# Micro_Bit_Gamer_Bit.net
KiCad netlist of a schematic drawn in EAGLE
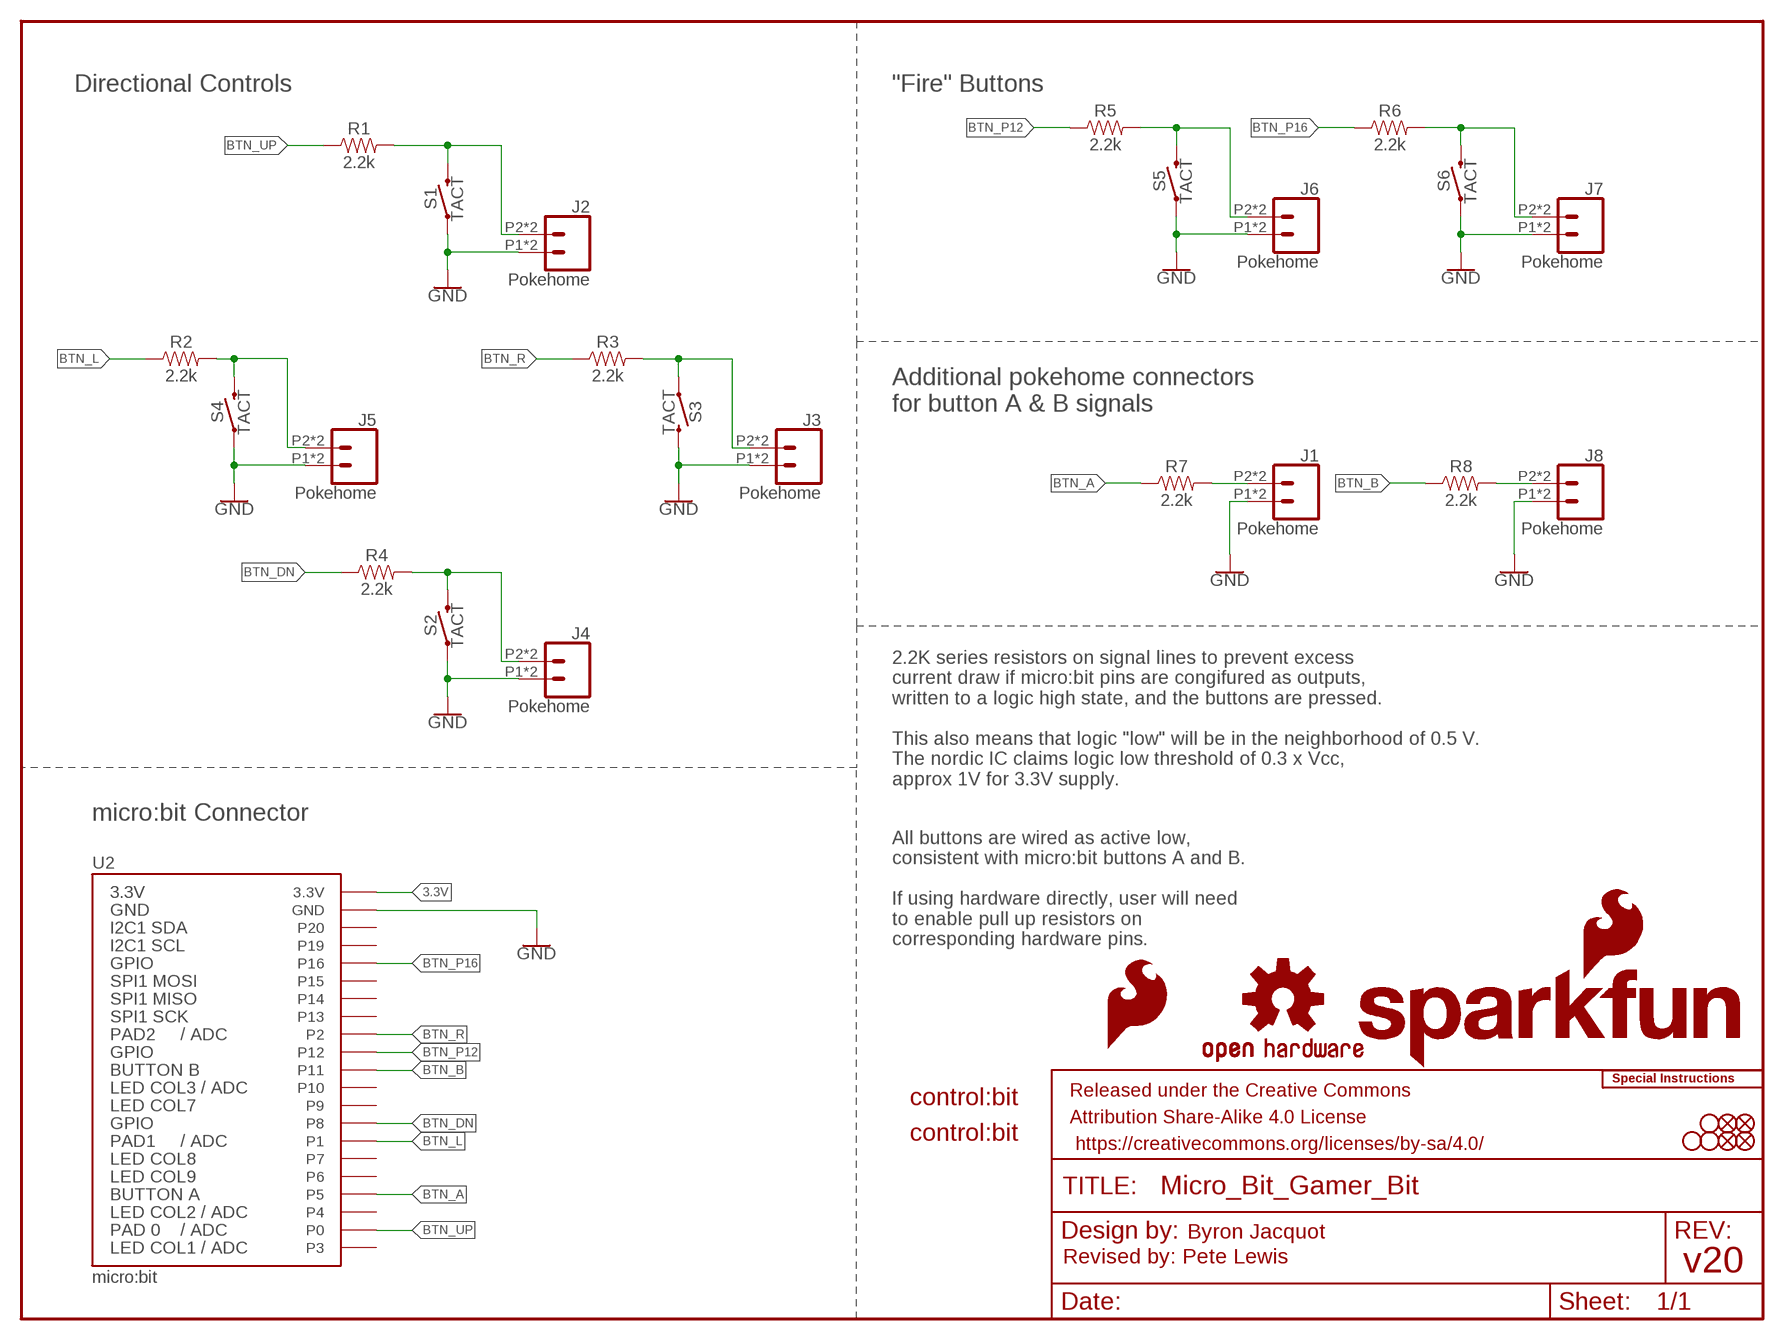
[diagram p0: schematic, sheet 1]

(export (version "E")
  (design (tool "Eeschema 10.0.6"))
  (components
    (comp (ref "FD1")
      (value "FIDUCIALUFIDUCIAL")
      (footprint "eagle-import:FIDUCIAL-MICRO")
      (libsource (lib "eagle-import") (part "FIDUCIALUFIDUCIAL"))
    )
    (comp (ref "FD2")
      (value "FIDUCIALUFIDUCIAL")
      (footprint "eagle-import:FIDUCIAL-MICRO")
      (libsource (lib "eagle-import") (part "FIDUCIALUFIDUCIAL"))
    )
    (comp (ref "FD3")
      (value "FIDUCIALUFIDUCIAL")
      (footprint "eagle-import:FIDUCIAL-MICRO")
      (libsource (lib "eagle-import") (part "FIDUCIALUFIDUCIAL"))
    )
    (comp (ref "FD4")
      (value "FIDUCIALUFIDUCIAL")
      (footprint "eagle-import:FIDUCIAL-MICRO")
      (libsource (lib "eagle-import") (part "FIDUCIALUFIDUCIAL"))
    )
    (comp (ref "FRAME1")
      (value "FRAME-LETTER")
      (footprint "eagle-import:CREATIVE_COMMONS")
      (libsource (lib "eagle-import") (part "FRAME-LETTER"))
    )
    (comp (ref "H1")
      (value "STAND-OFF")
      (footprint "eagle-import:STAND-OFF")
      (libsource (lib "eagle-import") (part "STAND-OFF"))
    )
    (comp (ref "H2")
      (value "STAND-OFF")
      (footprint "eagle-import:STAND-OFF")
      (libsource (lib "eagle-import") (part "STAND-OFF"))
    )
    (comp (ref "H3")
      (value "STAND-OFF")
      (footprint "eagle-import:STAND-OFF")
      (libsource (lib "eagle-import") (part "STAND-OFF"))
    )
    (comp (ref "J1")
      (value "Pokehome")
      (footprint "eagle-import:1X02_POKEHOME")
      (libsource (lib "eagle-import") (part "CONN_02SMALL_POKEHOME"))
    )
    (comp (ref "J2")
      (value "Pokehome")
      (footprint "eagle-import:1X02_POKEHOME")
      (libsource (lib "eagle-import") (part "CONN_02SMALL_POKEHOME"))
    )
    (comp (ref "J3")
      (value "Pokehome")
      (footprint "eagle-import:1X02_POKEHOME")
      (libsource (lib "eagle-import") (part "CONN_02SMALL_POKEHOME"))
    )
    (comp (ref "J4")
      (value "Pokehome")
      (footprint "eagle-import:1X02_POKEHOME")
      (libsource (lib "eagle-import") (part "CONN_02SMALL_POKEHOME"))
    )
    (comp (ref "J5")
      (value "Pokehome")
      (footprint "eagle-import:1X02_POKEHOME")
      (libsource (lib "eagle-import") (part "CONN_02SMALL_POKEHOME"))
    )
    (comp (ref "J6")
      (value "Pokehome")
      (footprint "eagle-import:1X02_POKEHOME")
      (libsource (lib "eagle-import") (part "CONN_02SMALL_POKEHOME"))
    )
    (comp (ref "J7")
      (value "Pokehome")
      (footprint "eagle-import:1X02_POKEHOME")
      (libsource (lib "eagle-import") (part "CONN_02SMALL_POKEHOME"))
    )
    (comp (ref "J8")
      (value "Pokehome")
      (footprint "eagle-import:1X02_POKEHOME")
      (libsource (lib "eagle-import") (part "CONN_02SMALL_POKEHOME"))
    )
    (comp (ref "LOGO1")
      (value "SFE_LOGO_FLAME.2_INCH")
      (footprint "eagle-import:SFE_LOGO_FLAME_.2")
      (libsource (lib "eagle-import") (part "SFE_LOGO_FLAME.2_INCH"))
    )
    (comp (ref "LOGO2")
      (value "OSHW-LOGOL")
      (footprint "eagle-import:OSHW-LOGO-L")
      (libsource (lib "eagle-import") (part "OSHW-LOGOL"))
    )
    (comp (ref "LOGO3")
      (value "SFE_LOGO_NAME_FLAME.3_INCH")
      (footprint "eagle-import:SFE_LOGO_NAME_FLAME_.3")
      (libsource (lib "eagle-import") (part "SFE_LOGO_NAME_FLAME.3_INCH"))
    )
    (comp (ref "R1")
      (value "2.2k")
      (footprint "eagle-import:0603")
      (libsource (lib "eagle-import") (part "2.2KOHM-0603-1/10W-1%"))
    )
    (comp (ref "R2")
      (value "2.2k")
      (footprint "eagle-import:0603")
      (libsource (lib "eagle-import") (part "2.2KOHM-0603-1/10W-1%"))
    )
    (comp (ref "R3")
      (value "2.2k")
      (footprint "eagle-import:0603")
      (libsource (lib "eagle-import") (part "2.2KOHM-0603-1/10W-1%"))
    )
    (comp (ref "R4")
      (value "2.2k")
      (footprint "eagle-import:0603")
      (libsource (lib "eagle-import") (part "2.2KOHM-0603-1/10W-1%"))
    )
    (comp (ref "R5")
      (value "2.2k")
      (footprint "eagle-import:0603")
      (libsource (lib "eagle-import") (part "2.2KOHM-0603-1/10W-1%"))
    )
    (comp (ref "R6")
      (value "2.2k")
      (footprint "eagle-import:0603")
      (libsource (lib "eagle-import") (part "2.2KOHM-0603-1/10W-1%"))
    )
    (comp (ref "R7")
      (value "2.2k")
      (footprint "eagle-import:0603")
      (libsource (lib "eagle-import") (part "2.2KOHM-0603-1/10W-1%"))
    )
    (comp (ref "R8")
      (value "2.2k")
      (footprint "eagle-import:0603")
      (libsource (lib "eagle-import") (part "2.2KOHM-0603-1/10W-1%"))
    )
    (comp (ref "S1")
      (value "TACT")
      (footprint "eagle-import:TACTILE_SWITCH_SMD_12MM")
      (libsource (lib "eagle-import") (part "MOMENTARY-SWITCH-SPST-SMD-12MM"))
    )
    (comp (ref "S2")
      (value "TACT")
      (footprint "eagle-import:TACTILE_SWITCH_SMD_12MM")
      (libsource (lib "eagle-import") (part "MOMENTARY-SWITCH-SPST-SMD-12MM"))
    )
    (comp (ref "S3")
      (value "TACT")
      (footprint "eagle-import:TACTILE_SWITCH_SMD_12MM")
      (libsource (lib "eagle-import") (part "MOMENTARY-SWITCH-SPST-SMD-12MM"))
    )
    (comp (ref "S4")
      (value "TACT")
      (footprint "eagle-import:TACTILE_SWITCH_SMD_12MM")
      (libsource (lib "eagle-import") (part "MOMENTARY-SWITCH-SPST-SMD-12MM"))
    )
    (comp (ref "S5")
      (value "TACT")
      (footprint "eagle-import:TACTILE_SWITCH_SMD_12MM")
      (libsource (lib "eagle-import") (part "MOMENTARY-SWITCH-SPST-SMD-12MM"))
    )
    (comp (ref "S6")
      (value "TACT")
      (footprint "eagle-import:TACTILE_SWITCH_SMD_12MM")
      (libsource (lib "eagle-import") (part "MOMENTARY-SWITCH-SPST-SMD-12MM"))
    )
    (comp (ref "U$1")
      (value "SPECIAL_INSTRUCTIONS-ORDERING")
      (footprint "eagle-import:ORDERING_INSTRUCTIONS")
      (libsource (lib "eagle-import") (part "SPECIAL_INSTRUCTIONS-ORDERING"))
    )
    (comp (ref "U$4")
      (value "LOGO-CONTROLBIT")
      (footprint "eagle-import:LOGO-CONTROLBIT")
      (libsource (lib "eagle-import") (part "LOGO-CONTROLBIT"))
    )
    (comp (ref "U$5")
      (value "LOGO-CONTROLBIT")
      (footprint "eagle-import:LOGO-CONTROLBIT")
      (libsource (lib "eagle-import") (part "LOGO-CONTROLBIT"))
    )
    (comp (ref "U2")
      (value "micro:bit")
      (footprint "eagle-import:MICRO_BIT-RA_SMD")
      (libsource (lib "eagle-import") (part "MICRO{colon}BIT?_RA"))
    )
  )
  (nets
    (net (code "1") (name "3.3V") (class "Default")
      (node (ref "U2") (pin "P$27") (pinfunction "3.3V_P$27") (pintype "bidirectional"))
      (node (ref "U2") (pin "P$28") (pinfunction "3.3V_P$28") (pintype "bidirectional"))
      (node (ref "U2") (pin "P$29") (pinfunction "3.3V_P$29") (pintype "bidirectional"))
      (node (ref "U2") (pin "P$30") (pinfunction "3.3V_P$30") (pintype "bidirectional"))
      (node (ref "U2") (pin "P$31") (pinfunction "3.3V_P$31") (pintype "bidirectional"))
      (node (ref "U2") (pin "P$32") (pinfunction "3.3V_P$32") (pintype "bidirectional"))
    )
    (net (code "2") (name "BTN_A") (class "Default")
      (node (ref "R7") (pin "1") (pinfunction "1_1") (pintype "passive"))
      (node (ref "U2") (pin "P$7") (pinfunction "P5_P$7") (pintype "bidirectional"))
    )
    (net (code "3") (name "BTN_B") (class "Default")
      (node (ref "R8") (pin "1") (pinfunction "1_1") (pintype "passive"))
      (node (ref "U2") (pin "P$17") (pinfunction "P11_P$17") (pintype "bidirectional"))
    )
    (net (code "4") (name "BTN_DN") (class "Default")
      (node (ref "R4") (pin "1") (pinfunction "1_1") (pintype "passive"))
      (node (ref "U2") (pin "P$14") (pinfunction "P8_P$14") (pintype "bidirectional"))
    )
    (net (code "5") (name "BTN_L") (class "Default")
      (node (ref "R2") (pin "1") (pinfunction "1_1") (pintype "passive"))
      (node (ref "U2") (pin "P$10") (pinfunction "P1_P$10") (pintype "bidirectional"))
      (node (ref "U2") (pin "P$11") (pinfunction "P1_P$11") (pintype "bidirectional"))
      (node (ref "U2") (pin "P$12") (pinfunction "P1_P$12") (pintype "bidirectional"))
      (node (ref "U2") (pin "P$13") (pinfunction "P1_P$13") (pintype "bidirectional"))
    )
    (net (code "6") (name "BTN_P12") (class "Default")
      (node (ref "R5") (pin "1") (pinfunction "1_1") (pintype "passive"))
      (node (ref "U2") (pin "P$18") (pinfunction "P12_P$18") (pintype "bidirectional"))
    )
    (net (code "7") (name "BTN_P16") (class "Default")
      (node (ref "R6") (pin "1") (pinfunction "1_1") (pintype "passive"))
      (node (ref "U2") (pin "P$26") (pinfunction "P16_P$26") (pintype "bidirectional"))
    )
    (net (code "8") (name "BTN_R") (class "Default")
      (node (ref "R3") (pin "1") (pinfunction "1_1") (pintype "passive"))
      (node (ref "U2") (pin "P$19") (pinfunction "P2_P$19") (pintype "bidirectional"))
      (node (ref "U2") (pin "P$20") (pinfunction "P2_P$20") (pintype "bidirectional"))
      (node (ref "U2") (pin "P$21") (pinfunction "P2_P$21") (pintype "bidirectional"))
      (node (ref "U2") (pin "P$22") (pinfunction "P2_P$22") (pintype "bidirectional"))
    )
    (net (code "9") (name "BTN_UP") (class "Default")
      (node (ref "R1") (pin "1") (pinfunction "1_1") (pintype "passive"))
      (node (ref "U2") (pin "P$2") (pinfunction "P0_P$2") (pintype "bidirectional"))
      (node (ref "U2") (pin "P$3") (pinfunction "P0_P$3") (pintype "bidirectional"))
      (node (ref "U2") (pin "P$4") (pinfunction "P0_P$4") (pintype "bidirectional"))
      (node (ref "U2") (pin "P$5") (pinfunction "P0_P$5") (pintype "bidirectional"))
    )
    (net (code "10") (name "GND") (class "Default")
      (node (ref "J1") (pin "P1") (pinfunction "1_P1") (pintype "passive"))
      (node (ref "J1") (pin "P3") (pinfunction "1_P3") (pintype "passive"))
      (node (ref "J2") (pin "P1") (pinfunction "1_P1") (pintype "passive"))
      (node (ref "J2") (pin "P3") (pinfunction "1_P3") (pintype "passive"))
      (node (ref "J3") (pin "P1") (pinfunction "1_P1") (pintype "passive"))
      (node (ref "J3") (pin "P3") (pinfunction "1_P3") (pintype "passive"))
      (node (ref "J4") (pin "P1") (pinfunction "1_P1") (pintype "passive"))
      (node (ref "J4") (pin "P3") (pinfunction "1_P3") (pintype "passive"))
      (node (ref "J5") (pin "P1") (pinfunction "1_P1") (pintype "passive"))
      (node (ref "J5") (pin "P3") (pinfunction "1_P3") (pintype "passive"))
      (node (ref "J6") (pin "P1") (pinfunction "1_P1") (pintype "passive"))
      (node (ref "J6") (pin "P3") (pinfunction "1_P3") (pintype "passive"))
      (node (ref "J7") (pin "P1") (pinfunction "1_P1") (pintype "passive"))
      (node (ref "J7") (pin "P3") (pinfunction "1_P3") (pintype "passive"))
      (node (ref "J8") (pin "P1") (pinfunction "1_P1") (pintype "passive"))
      (node (ref "J8") (pin "P3") (pinfunction "1_P3") (pintype "passive"))
      (node (ref "S1") (pin "1") (pinfunction "1_1") (pintype "passive"))
      (node (ref "S2") (pin "1") (pinfunction "1_1") (pintype "passive"))
      (node (ref "S3") (pin "3") (pinfunction "2_3") (pintype "passive"))
      (node (ref "S4") (pin "1") (pinfunction "1_1") (pintype "passive"))
      (node (ref "S5") (pin "1") (pinfunction "1_1") (pintype "passive"))
      (node (ref "S6") (pin "1") (pinfunction "1_1") (pintype "passive"))
      (node (ref "U2") (pin "P$35") (pinfunction "GND_P$35") (pintype "bidirectional"))
      (node (ref "U2") (pin "P$36") (pinfunction "GND_P$36") (pintype "bidirectional"))
      (node (ref "U2") (pin "P$37") (pinfunction "GND_P$37") (pintype "bidirectional"))
      (node (ref "U2") (pin "P$38") (pinfunction "GND_P$38") (pintype "bidirectional"))
      (node (ref "U2") (pin "P$39") (pinfunction "GND_P$39") (pintype "bidirectional"))
      (node (ref "U2") (pin "P$40") (pinfunction "GND_P$40") (pintype "bidirectional"))
    )
    (net (code "11") (name "Net-(J1-2-PadP2)") (class "Default")
      (node (ref "J1") (pin "P2") (pinfunction "2_P2") (pintype "passive"))
      (node (ref "J1") (pin "P4") (pinfunction "2_P4") (pintype "passive"))
      (node (ref "R7") (pin "2") (pinfunction "2_2") (pintype "passive"))
    )
    (net (code "12") (name "Net-(J3-2-PadP2)") (class "Default")
      (node (ref "J3") (pin "P2") (pinfunction "2_P2") (pintype "passive"))
      (node (ref "J3") (pin "P4") (pinfunction "2_P4") (pintype "passive"))
      (node (ref "R3") (pin "2") (pinfunction "2_2") (pintype "passive"))
      (node (ref "S3") (pin "1") (pinfunction "1_1") (pintype "passive"))
    )
    (net (code "13") (name "Net-(J8-2-PadP2)") (class "Default")
      (node (ref "J8") (pin "P2") (pinfunction "2_P2") (pintype "passive"))
      (node (ref "J8") (pin "P4") (pinfunction "2_P4") (pintype "passive"))
      (node (ref "R8") (pin "2") (pinfunction "2_2") (pintype "passive"))
    )
    (net (code "14") (name "Net-(S1-2)") (class "Default")
      (node (ref "J2") (pin "P2") (pinfunction "2_P2") (pintype "passive"))
      (node (ref "J2") (pin "P4") (pinfunction "2_P4") (pintype "passive"))
      (node (ref "R1") (pin "2") (pinfunction "2_2") (pintype "passive"))
      (node (ref "S1") (pin "3") (pinfunction "2_3") (pintype "passive"))
    )
    (net (code "15") (name "Net-(S2-2)") (class "Default")
      (node (ref "J4") (pin "P2") (pinfunction "2_P2") (pintype "passive"))
      (node (ref "J4") (pin "P4") (pinfunction "2_P4") (pintype "passive"))
      (node (ref "R4") (pin "2") (pinfunction "2_2") (pintype "passive"))
      (node (ref "S2") (pin "3") (pinfunction "2_3") (pintype "passive"))
    )
    (net (code "16") (name "Net-(S4-2)") (class "Default")
      (node (ref "J5") (pin "P2") (pinfunction "2_P2") (pintype "passive"))
      (node (ref "J5") (pin "P4") (pinfunction "2_P4") (pintype "passive"))
      (node (ref "R2") (pin "2") (pinfunction "2_2") (pintype "passive"))
      (node (ref "S4") (pin "3") (pinfunction "2_3") (pintype "passive"))
    )
    (net (code "17") (name "Net-(S5-2)") (class "Default")
      (node (ref "J6") (pin "P2") (pinfunction "2_P2") (pintype "passive"))
      (node (ref "J6") (pin "P4") (pinfunction "2_P4") (pintype "passive"))
      (node (ref "R5") (pin "2") (pinfunction "2_2") (pintype "passive"))
      (node (ref "S5") (pin "3") (pinfunction "2_3") (pintype "passive"))
    )
    (net (code "18") (name "Net-(S6-2)") (class "Default")
      (node (ref "J7") (pin "P2") (pinfunction "2_P2") (pintype "passive"))
      (node (ref "J7") (pin "P4") (pinfunction "2_P4") (pintype "passive"))
      (node (ref "R6") (pin "2") (pinfunction "2_2") (pintype "passive"))
      (node (ref "S6") (pin "3") (pinfunction "2_3") (pintype "passive"))
    )
    (net (code "19") (name "unconnected-(U2-P3-PadP$1)") (class "Default")
      (node (ref "U2") (pin "P$1") (pinfunction "P3_P$1") (pintype "bidirectional"))
    )
    (net (code "20") (name "unconnected-(U2-P4-PadP$6)") (class "Default")
      (node (ref "U2") (pin "P$6") (pinfunction "P4_P$6") (pintype "bidirectional"))
    )
    (net (code "21") (name "unconnected-(U2-P6-PadP$8)") (class "Default")
      (node (ref "U2") (pin "P$8") (pinfunction "P6_P$8") (pintype "bidirectional"))
    )
    (net (code "22") (name "unconnected-(U2-P7-PadP$9)") (class "Default")
      (node (ref "U2") (pin "P$9") (pinfunction "P7_P$9") (pintype "bidirectional"))
    )
    (net (code "23") (name "unconnected-(U2-P9-PadP$15)") (class "Default")
      (node (ref "U2") (pin "P$15") (pinfunction "P9_P$15") (pintype "bidirectional"))
    )
    (net (code "24") (name "unconnected-(U2-P10-PadP$16)") (class "Default")
      (node (ref "U2") (pin "P$16") (pinfunction "P10_P$16") (pintype "bidirectional"))
    )
    (net (code "25") (name "unconnected-(U2-P13-PadP$23)") (class "Default")
      (node (ref "U2") (pin "P$23") (pinfunction "P13_P$23") (pintype "bidirectional"))
    )
    (net (code "26") (name "unconnected-(U2-P14-PadP$24)") (class "Default")
      (node (ref "U2") (pin "P$24") (pinfunction "P14_P$24") (pintype "bidirectional"))
    )
    (net (code "27") (name "unconnected-(U2-P15-PadP$25)") (class "Default")
      (node (ref "U2") (pin "P$25") (pinfunction "P15_P$25") (pintype "bidirectional"))
    )
    (net (code "28") (name "unconnected-(U2-P19-PadP$33)") (class "Default")
      (node (ref "U2") (pin "P$33") (pinfunction "P19_P$33") (pintype "bidirectional"))
    )
    (net (code "29") (name "unconnected-(U2-P20-PadP$34)") (class "Default")
      (node (ref "U2") (pin "P$34") (pinfunction "P20_P$34") (pintype "bidirectional"))
    )
  )
)
